# tube-driver_sch-pcb.net
KiCad netlist of a schematic drawn in EAGLE
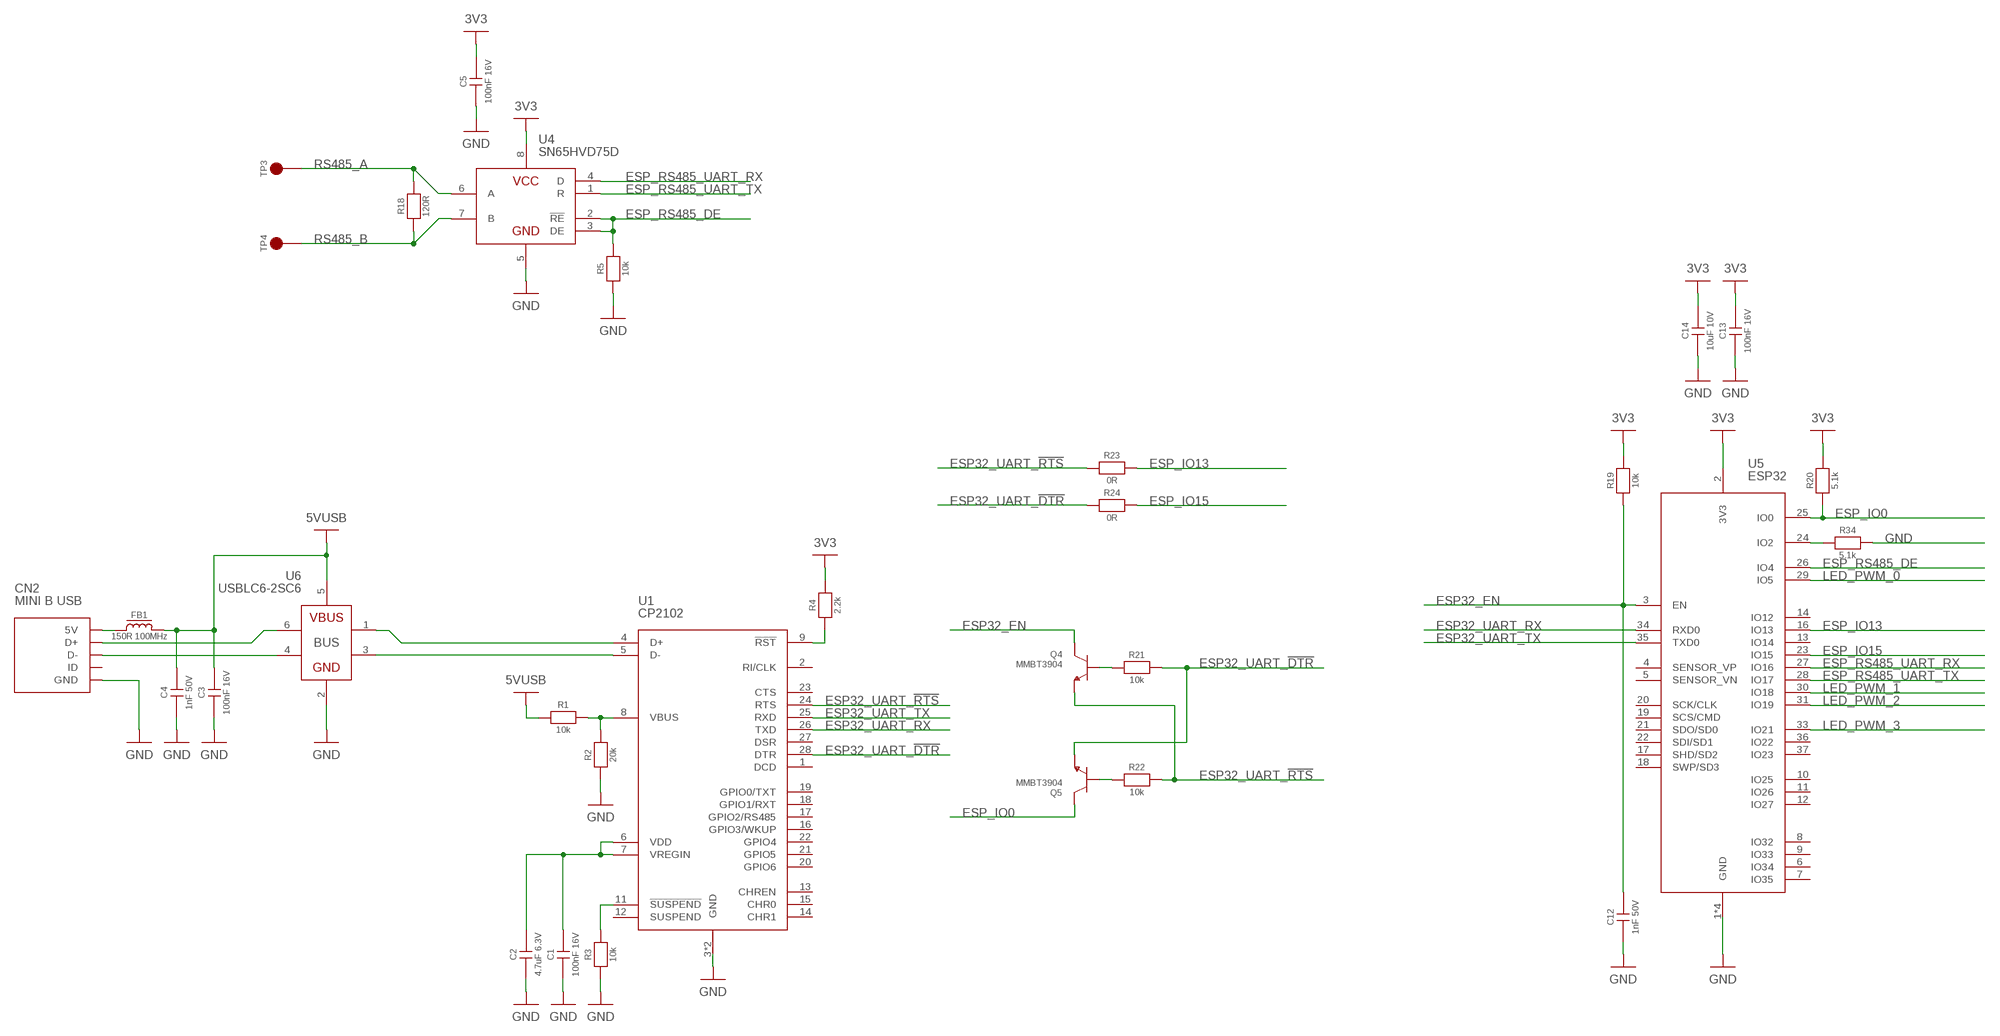
[diagram p0: schematic, sheet 1]
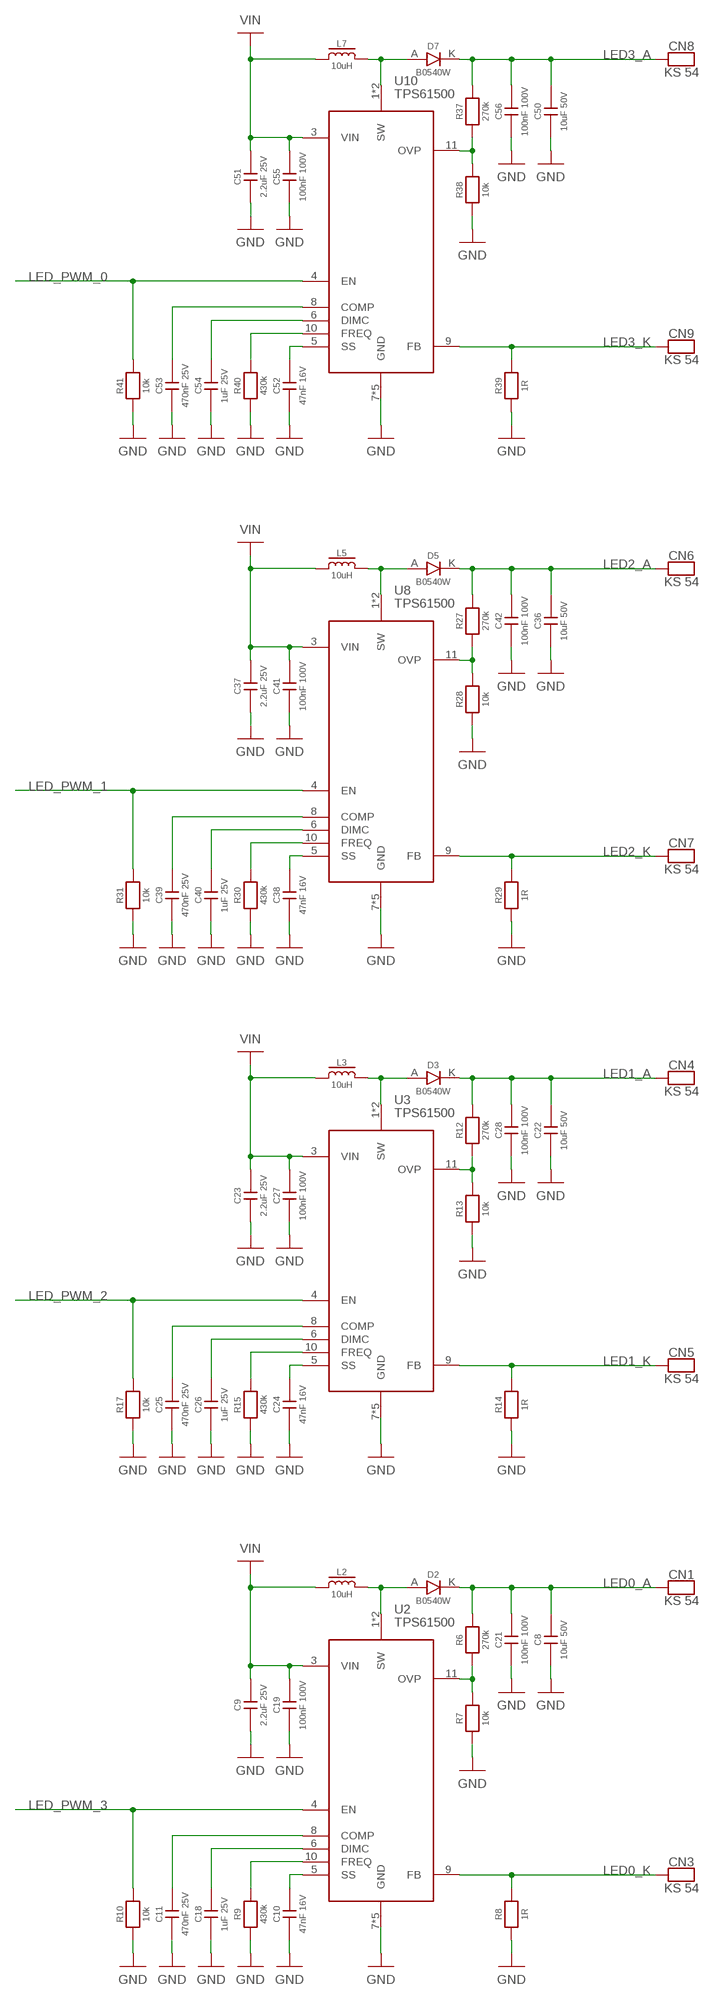
[diagram p1: schematic, sheet 2]
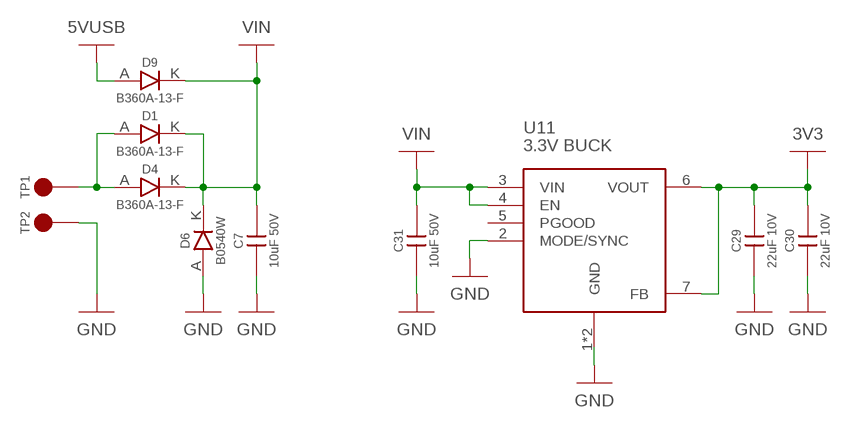
[diagram p2: schematic, sheet 3]
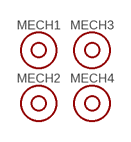
[diagram p3: schematic, sheet 4]

(export (version "E")
  (design (tool "Eeschema 10.0.6"))
  (components
    (comp (ref "C1")
      (value "100nF 16V")
      (footprint "eagle-import:0603")
      (libsource (lib "eagle-import") (part "CL10B104KO8WPNC"))
    )
    (comp (ref "C2")
      (value "4.7uF 6.3V")
      (footprint "eagle-import:0603")
      (libsource (lib "eagle-import") (part "GRM188R60J475ME19D"))
    )
    (comp (ref "C3")
      (value "100nF 16V")
      (footprint "eagle-import:0603")
      (libsource (lib "eagle-import") (part "CL10B104KO8WPNC"))
    )
    (comp (ref "C4")
      (value "1nF 50V")
      (footprint "eagle-import:0603")
      (libsource (lib "eagle-import") (part "CL10B102KB8NNNC"))
    )
    (comp (ref "C5")
      (value "100nF 16V")
      (footprint "eagle-import:0603")
      (libsource (lib "eagle-import") (part "CL10B104KO8WPNC"))
    )
    (comp (ref "C12")
      (value "1nF 50V")
      (footprint "eagle-import:0603")
      (libsource (lib "eagle-import") (part "CL10B102KB8NNNC"))
    )
    (comp (ref "C13")
      (value "100nF 16V")
      (footprint "eagle-import:0603")
      (libsource (lib "eagle-import") (part "CL10B104KO8WPNC"))
    )
    (comp (ref "C14")
      (value "10uF 10V")
      (footprint "eagle-import:0603")
      (libsource (lib "eagle-import") (part "GRM188R61A106KE69D"))
    )
    (comp (ref "CN2")
      (value "MINI B USB")
      (footprint "eagle-import:MUSB-05-S-B-SM-A")
      (libsource (lib "eagle-import") (part "MUSB-05-S-B-SM-A"))
    )
    (comp (ref "FB1")
      (value "150R 100MHz")
      (footprint "eagle-import:1206")
      (libsource (lib "eagle-import") (part "ILB1206ER151V"))
    )
    (comp (ref "Q4")
      (value "MMBT3904")
      (footprint "eagle-import:SOT23-3")
      (libsource (lib "eagle-import") (part "MMBT3904-7-F"))
    )
    (comp (ref "Q5")
      (value "MMBT3904")
      (footprint "eagle-import:SOT23-3")
      (libsource (lib "eagle-import") (part "MMBT3904-7-F"))
    )
    (comp (ref "R1")
      (value "10k")
      (footprint "eagle-import:0603")
      (libsource (lib "eagle-import") (part "ERJ3EKF1002V"))
    )
    (comp (ref "R2")
      (value "20k")
      (footprint "eagle-import:0603")
      (libsource (lib "eagle-import") (part "ERJ3EKF2002V"))
    )
    (comp (ref "R3")
      (value "10k")
      (footprint "eagle-import:0603")
      (libsource (lib "eagle-import") (part "ERJ3EKF1002V"))
    )
    (comp (ref "R4")
      (value "2.2k")
      (footprint "eagle-import:0603")
      (libsource (lib "eagle-import") (part "ERJ3EKF2201V"))
    )
    (comp (ref "R5")
      (value "10k")
      (footprint "eagle-import:0603")
      (libsource (lib "eagle-import") (part "ERJ3EKF1002V"))
    )
    (comp (ref "R18")
      (value "120R")
      (footprint "eagle-import:0603")
      (libsource (lib "eagle-import") (part "ERJ3EKF1200V"))
    )
    (comp (ref "R19")
      (value "10k")
      (footprint "eagle-import:0603")
      (libsource (lib "eagle-import") (part "ERJ3EKF1002V"))
    )
    (comp (ref "R20")
      (value "5.1k")
      (footprint "eagle-import:0603")
      (libsource (lib "eagle-import") (part "ERJ3EKF5101V"))
    )
    (comp (ref "R21")
      (value "10k")
      (footprint "eagle-import:0603")
      (libsource (lib "eagle-import") (part "ERJ3EKF1002V"))
    )
    (comp (ref "R22")
      (value "10k")
      (footprint "eagle-import:0603")
      (libsource (lib "eagle-import") (part "ERJ3EKF1002V"))
    )
    (comp (ref "R23")
      (value "0R")
      (footprint "eagle-import:0603")
      (libsource (lib "eagle-import") (part "CRCW06030000Z0EA"))
    )
    (comp (ref "R24")
      (value "0R")
      (footprint "eagle-import:0603")
      (libsource (lib "eagle-import") (part "CRCW06030000Z0EA"))
    )
    (comp (ref "R34")
      (value "5.1k")
      (footprint "eagle-import:0603")
      (libsource (lib "eagle-import") (part "ERJ3EKF5101V"))
    )
    (comp (ref "TP3")
      (value "2MM_TEST_POINT")
      (footprint "eagle-import:2MM_TEST_PAD")
      (libsource (lib "eagle-import") (part "2MM_TEST_POINT"))
    )
    (comp (ref "TP4")
      (value "2MM_TEST_POINT")
      (footprint "eagle-import:2MM_TEST_PAD")
      (libsource (lib "eagle-import") (part "2MM_TEST_POINT"))
    )
    (comp (ref "U1")
      (value "CP2102")
      (footprint "eagle-import:QFN28")
      (libsource (lib "eagle-import") (part "CP2102N-A01-GQFN28"))
    )
    (comp (ref "U4")
      (value "SN65HVD75D")
      (footprint "eagle-import:SO8")
      (libsource (lib "eagle-import") (part "SN65HVD75D"))
    )
    (comp (ref "U5")
      (value "ESP32")
      (footprint "eagle-import:ESP32-WROOM-32D")
      (libsource (lib "eagle-import") (part "ESP32-WROOM-32D"))
    )
    (comp (ref "U6")
      (value "USBLC6-2SC6")
      (footprint "eagle-import:SOT23-6")
      (libsource (lib "eagle-import") (part "USBLC6-2SC6"))
    )
    (comp (ref "MECH1")
      (value "6mm x 3mm")
      (footprint "eagle-import:MOUNTHOLE_6X3")
      (libsource (lib "eagle-import") (part "MOUNTHOLE"))
    )
    (comp (ref "MECH2")
      (value "6mm x 3mm")
      (footprint "eagle-import:MOUNTHOLE_6X3")
      (libsource (lib "eagle-import") (part "MOUNTHOLE"))
    )
    (comp (ref "MECH3")
      (value "6mm x 3mm")
      (footprint "eagle-import:MOUNTHOLE_6X3")
      (libsource (lib "eagle-import") (part "MOUNTHOLE"))
    )
    (comp (ref "MECH4")
      (value "6mm x 3mm")
      (footprint "eagle-import:MOUNTHOLE_6X3")
      (libsource (lib "eagle-import") (part "MOUNTHOLE"))
    )
    (comp (ref "C7")
      (value "10uF 50V")
      (footprint "eagle-import:1210")
      (libsource (lib "eagle-import") (part "C3225X7S1H106M250AB"))
    )
    (comp (ref "C29")
      (value "22uF 10V")
      (footprint "eagle-import:1206")
      (libsource (lib "eagle-import") (part "CL31B226MPHNNNE"))
    )
    (comp (ref "C30")
      (value "22uF 10V")
      (footprint "eagle-import:1206")
      (libsource (lib "eagle-import") (part "CL31B226MPHNNNE"))
    )
    (comp (ref "C31")
      (value "10uF 50V")
      (footprint "eagle-import:1210")
      (libsource (lib "eagle-import") (part "C3225X7S1H106M250AB"))
    )
    (comp (ref "D1")
      (value "B360A-13-F")
      (footprint "eagle-import:DO214AC")
      (libsource (lib "eagle-import") (part "B360A-13-F"))
    )
    (comp (ref "D4")
      (value "B360A-13-F")
      (footprint "eagle-import:DO214AC")
      (libsource (lib "eagle-import") (part "B360A-13-F"))
    )
    (comp (ref "D6")
      (value "B0540W")
      (footprint "eagle-import:SOD-123")
      (libsource (lib "eagle-import") (part "B0540W"))
    )
    (comp (ref "D9")
      (value "B360A-13-F")
      (footprint "eagle-import:DO214AC")
      (libsource (lib "eagle-import") (part "B360A-13-F"))
    )
    (comp (ref "TP1")
      (value "2MM_TEST_POINT")
      (footprint "eagle-import:2MM_TEST_PAD")
      (libsource (lib "eagle-import") (part "2MM_TEST_POINT"))
    )
    (comp (ref "TP2")
      (value "2MM_TEST_POINT")
      (footprint "eagle-import:2MM_TEST_PAD")
      (libsource (lib "eagle-import") (part "2MM_TEST_POINT"))
    )
    (comp (ref "U11")
      (value "3.3V BUCK")
      (footprint "eagle-import:TI_MICROSIP_10")
      (libsource (lib "eagle-import") (part "LMZM23600V3SILT"))
    )
    (comp (ref "C8")
      (value "10uF 50V")
      (footprint "eagle-import:1210")
      (libsource (lib "eagle-import") (part "C3225X7S1H106M250AB"))
    )
    (comp (ref "C9")
      (value "2.2uF 25V")
      (footprint "eagle-import:0603")
      (libsource (lib "eagle-import") (part "GRM188R61E225KA12D"))
    )
    (comp (ref "C10")
      (value "47nF 16V")
      (footprint "eagle-import:0603")
      (libsource (lib "eagle-import") (part "CL10B473KO8NNNC"))
    )
    (comp (ref "C11")
      (value "470nF 25V")
      (footprint "eagle-import:0603")
      (libsource (lib "eagle-import") (part "GRM188R71E474KA12D"))
    )
    (comp (ref "C18")
      (value "1uF 25V")
      (footprint "eagle-import:0603")
      (libsource (lib "eagle-import") (part "CL10A105KA8NNNC"))
    )
    (comp (ref "C19")
      (value "100nF 100V")
      (footprint "eagle-import:0603")
      (libsource (lib "eagle-import") (part "06031C104KAT2A"))
    )
    (comp (ref "C21")
      (value "100nF 100V")
      (footprint "eagle-import:0603")
      (libsource (lib "eagle-import") (part "06031C104KAT2A"))
    )
    (comp (ref "C22")
      (value "10uF 50V")
      (footprint "eagle-import:1210")
      (libsource (lib "eagle-import") (part "C3225X7S1H106M250AB"))
    )
    (comp (ref "C23")
      (value "2.2uF 25V")
      (footprint "eagle-import:0603")
      (libsource (lib "eagle-import") (part "GRM188R61E225KA12D"))
    )
    (comp (ref "C24")
      (value "47nF 16V")
      (footprint "eagle-import:0603")
      (libsource (lib "eagle-import") (part "CL10B473KO8NNNC"))
    )
    (comp (ref "C25")
      (value "470nF 25V")
      (footprint "eagle-import:0603")
      (libsource (lib "eagle-import") (part "GRM188R71E474KA12D"))
    )
    (comp (ref "C26")
      (value "1uF 25V")
      (footprint "eagle-import:0603")
      (libsource (lib "eagle-import") (part "CL10A105KA8NNNC"))
    )
    (comp (ref "C27")
      (value "100nF 100V")
      (footprint "eagle-import:0603")
      (libsource (lib "eagle-import") (part "06031C104KAT2A"))
    )
    (comp (ref "C28")
      (value "100nF 100V")
      (footprint "eagle-import:0603")
      (libsource (lib "eagle-import") (part "06031C104KAT2A"))
    )
    (comp (ref "C36")
      (value "10uF 50V")
      (footprint "eagle-import:1210")
      (libsource (lib "eagle-import") (part "C3225X7S1H106M250AB"))
    )
    (comp (ref "C37")
      (value "2.2uF 25V")
      (footprint "eagle-import:0603")
      (libsource (lib "eagle-import") (part "GRM188R61E225KA12D"))
    )
    (comp (ref "C38")
      (value "47nF 16V")
      (footprint "eagle-import:0603")
      (libsource (lib "eagle-import") (part "CL10B473KO8NNNC"))
    )
    (comp (ref "C39")
      (value "470nF 25V")
      (footprint "eagle-import:0603")
      (libsource (lib "eagle-import") (part "GRM188R71E474KA12D"))
    )
    (comp (ref "C40")
      (value "1uF 25V")
      (footprint "eagle-import:0603")
      (libsource (lib "eagle-import") (part "CL10A105KA8NNNC"))
    )
    (comp (ref "C41")
      (value "100nF 100V")
      (footprint "eagle-import:0603")
      (libsource (lib "eagle-import") (part "06031C104KAT2A"))
    )
    (comp (ref "C42")
      (value "100nF 100V")
      (footprint "eagle-import:0603")
      (libsource (lib "eagle-import") (part "06031C104KAT2A"))
    )
    (comp (ref "C50")
      (value "10uF 50V")
      (footprint "eagle-import:1210")
      (libsource (lib "eagle-import") (part "C3225X7S1H106M250AB"))
    )
    (comp (ref "C51")
      (value "2.2uF 25V")
      (footprint "eagle-import:0603")
      (libsource (lib "eagle-import") (part "GRM188R61E225KA12D"))
    )
    (comp (ref "C52")
      (value "47nF 16V")
      (footprint "eagle-import:0603")
      (libsource (lib "eagle-import") (part "CL10B473KO8NNNC"))
    )
    (comp (ref "C53")
      (value "470nF 25V")
      (footprint "eagle-import:0603")
      (libsource (lib "eagle-import") (part "GRM188R71E474KA12D"))
    )
    (comp (ref "C54")
      (value "1uF 25V")
      (footprint "eagle-import:0603")
      (libsource (lib "eagle-import") (part "CL10A105KA8NNNC"))
    )
    (comp (ref "C55")
      (value "100nF 100V")
      (footprint "eagle-import:0603")
      (libsource (lib "eagle-import") (part "06031C104KAT2A"))
    )
    (comp (ref "C56")
      (value "100nF 100V")
      (footprint "eagle-import:0603")
      (libsource (lib "eagle-import") (part "06031C104KAT2A"))
    )
    (comp (ref "CN1")
      (value "KS 54")
      (footprint "eagle-import:KEYSTONE_54")
      (libsource (lib "eagle-import") (part "KEYSTONE_54"))
    )
    (comp (ref "CN3")
      (value "KS 54")
      (footprint "eagle-import:KEYSTONE_54")
      (libsource (lib "eagle-import") (part "KEYSTONE_54"))
    )
    (comp (ref "CN4")
      (value "KS 54")
      (footprint "eagle-import:KEYSTONE_54")
      (libsource (lib "eagle-import") (part "KEYSTONE_54"))
    )
    (comp (ref "CN5")
      (value "KS 54")
      (footprint "eagle-import:KEYSTONE_54")
      (libsource (lib "eagle-import") (part "KEYSTONE_54"))
    )
    (comp (ref "CN6")
      (value "KS 54")
      (footprint "eagle-import:KEYSTONE_54")
      (libsource (lib "eagle-import") (part "KEYSTONE_54"))
    )
    (comp (ref "CN7")
      (value "KS 54")
      (footprint "eagle-import:KEYSTONE_54")
      (libsource (lib "eagle-import") (part "KEYSTONE_54"))
    )
    (comp (ref "CN8")
      (value "KS 54")
      (footprint "eagle-import:KEYSTONE_54")
      (libsource (lib "eagle-import") (part "KEYSTONE_54"))
    )
    (comp (ref "CN9")
      (value "KS 54")
      (footprint "eagle-import:KEYSTONE_54")
      (libsource (lib "eagle-import") (part "KEYSTONE_54"))
    )
    (comp (ref "D2")
      (value "B0540W")
      (footprint "eagle-import:SOD-123")
      (libsource (lib "eagle-import") (part "B0540W"))
    )
    (comp (ref "D3")
      (value "B0540W")
      (footprint "eagle-import:SOD-123")
      (libsource (lib "eagle-import") (part "B0540W"))
    )
    (comp (ref "D5")
      (value "B0540W")
      (footprint "eagle-import:SOD-123")
      (libsource (lib "eagle-import") (part "B0540W"))
    )
    (comp (ref "D7")
      (value "B0540W")
      (footprint "eagle-import:SOD-123")
      (libsource (lib "eagle-import") (part "B0540W"))
    )
    (comp (ref "L2")
      (value "10uH")
      (footprint "eagle-import:SRN6045")
      (libsource (lib "eagle-import") (part "SRN6045-100M"))
    )
    (comp (ref "L3")
      (value "10uH")
      (footprint "eagle-import:SRN6045")
      (libsource (lib "eagle-import") (part "SRN6045-100M"))
    )
    (comp (ref "L5")
      (value "10uH")
      (footprint "eagle-import:SRN6045")
      (libsource (lib "eagle-import") (part "SRN6045-100M"))
    )
    (comp (ref "L7")
      (value "10uH")
      (footprint "eagle-import:SRN6045")
      (libsource (lib "eagle-import") (part "SRN6045-100M"))
    )
    (comp (ref "R6")
      (value "270k")
      (footprint "eagle-import:0603")
      (libsource (lib "eagle-import") (part "ERJ3EKF2703V"))
    )
    (comp (ref "R7")
      (value "10k")
      (footprint "eagle-import:0603")
      (libsource (lib "eagle-import") (part "ERJ3EKF1002V"))
    )
    (comp (ref "R8")
      (value "1R")
      (footprint "eagle-import:1206")
      (libsource (lib "eagle-import") (part "CRCW12061R00FKEA"))
    )
    (comp (ref "R9")
      (value "430k")
      (footprint "eagle-import:0603")
      (libsource (lib "eagle-import") (part "ERJ3EKF4303V"))
    )
    (comp (ref "R10")
      (value "10k")
      (footprint "eagle-import:0603")
      (libsource (lib "eagle-import") (part "ERJ3EKF1002V"))
    )
    (comp (ref "R12")
      (value "270k")
      (footprint "eagle-import:0603")
      (libsource (lib "eagle-import") (part "ERJ3EKF2703V"))
    )
    (comp (ref "R13")
      (value "10k")
      (footprint "eagle-import:0603")
      (libsource (lib "eagle-import") (part "ERJ3EKF1002V"))
    )
    (comp (ref "R14")
      (value "1R")
      (footprint "eagle-import:1206")
      (libsource (lib "eagle-import") (part "CRCW12061R00FKEA"))
    )
    (comp (ref "R15")
      (value "430k")
      (footprint "eagle-import:0603")
      (libsource (lib "eagle-import") (part "ERJ3EKF4303V"))
    )
    (comp (ref "R17")
      (value "10k")
      (footprint "eagle-import:0603")
      (libsource (lib "eagle-import") (part "ERJ3EKF1002V"))
    )
    (comp (ref "R27")
      (value "270k")
      (footprint "eagle-import:0603")
      (libsource (lib "eagle-import") (part "ERJ3EKF2703V"))
    )
    (comp (ref "R28")
      (value "10k")
      (footprint "eagle-import:0603")
      (libsource (lib "eagle-import") (part "ERJ3EKF1002V"))
    )
    (comp (ref "R29")
      (value "1R")
      (footprint "eagle-import:1206")
      (libsource (lib "eagle-import") (part "CRCW12061R00FKEA"))
    )
    (comp (ref "R30")
      (value "430k")
      (footprint "eagle-import:0603")
      (libsource (lib "eagle-import") (part "ERJ3EKF4303V"))
    )
    (comp (ref "R31")
      (value "10k")
      (footprint "eagle-import:0603")
      (libsource (lib "eagle-import") (part "ERJ3EKF1002V"))
    )
    (comp (ref "R37")
      (value "270k")
      (footprint "eagle-import:0603")
      (libsource (lib "eagle-import") (part "ERJ3EKF2703V"))
    )
    (comp (ref "R38")
      (value "10k")
      (footprint "eagle-import:0603")
      (libsource (lib "eagle-import") (part "ERJ3EKF1002V"))
    )
    (comp (ref "R39")
      (value "1R")
      (footprint "eagle-import:1206")
      (libsource (lib "eagle-import") (part "CRCW12061R00FKEA"))
    )
    (comp (ref "R40")
      (value "430k")
      (footprint "eagle-import:0603")
      (libsource (lib "eagle-import") (part "ERJ3EKF4303V"))
    )
    (comp (ref "R41")
      (value "10k")
      (footprint "eagle-import:0603")
      (libsource (lib "eagle-import") (part "ERJ3EKF1002V"))
    )
    (comp (ref "U2")
      (value "TPS61500")
      (footprint "eagle-import:HTSSOP14-4.5")
      (libsource (lib "eagle-import") (part "TPS61500"))
    )
    (comp (ref "U3")
      (value "TPS61500")
      (footprint "eagle-import:HTSSOP14-4.5")
      (libsource (lib "eagle-import") (part "TPS61500"))
    )
    (comp (ref "U8")
      (value "TPS61500")
      (footprint "eagle-import:HTSSOP14-4.5")
      (libsource (lib "eagle-import") (part "TPS61500"))
    )
    (comp (ref "U10")
      (value "TPS61500")
      (footprint "eagle-import:HTSSOP14-4.5")
      (libsource (lib "eagle-import") (part "TPS61500"))
    )
  )
  (nets
    (net (code "1") (name "3V3") (class "Default")
      (node (ref "C13") (pin "2") (pinfunction "2_2") (pintype "bidirectional"))
      (node (ref "C14") (pin "2") (pinfunction "2_2") (pintype "bidirectional"))
      (node (ref "C29") (pin "2") (pinfunction "2_2") (pintype "bidirectional"))
      (node (ref "C30") (pin "2") (pinfunction "2_2") (pintype "bidirectional"))
      (node (ref "C5") (pin "2") (pinfunction "2_2") (pintype "bidirectional"))
      (node (ref "R19") (pin "2") (pinfunction "2_2") (pintype "bidirectional"))
      (node (ref "R20") (pin "2") (pinfunction "2_2") (pintype "bidirectional"))
      (node (ref "R4") (pin "2") (pinfunction "2_2") (pintype "bidirectional"))
      (node (ref "U11") (pin "6") (pinfunction "VOUT_6") (pintype "bidirectional"))
      (node (ref "U11") (pin "7") (pinfunction "FB_7") (pintype "bidirectional"))
      (node (ref "U4") (pin "8") (pinfunction "VCC_8") (pintype "bidirectional"))
      (node (ref "U5") (pin "2") (pinfunction "3V3_2") (pintype "bidirectional"))
    )
    (net (code "2") (name "5VUSB") (class "Default")
      (node (ref "C3") (pin "2") (pinfunction "2_2") (pintype "bidirectional"))
      (node (ref "C4") (pin "2") (pinfunction "2_2") (pintype "bidirectional"))
      (node (ref "D9") (pin "A") (pinfunction "A_A") (pintype "bidirectional"))
      (node (ref "FB1") (pin "2") (pinfunction "2_2") (pintype "bidirectional"))
      (node (ref "R1") (pin "1") (pinfunction "1_1") (pintype "bidirectional"))
      (node (ref "U6") (pin "5") (pinfunction "VBUS_5") (pintype "bidirectional"))
    )
    (net (code "3") (name "ESP32_EN") (class "Default")
      (node (ref "C12") (pin "2") (pinfunction "2_2") (pintype "bidirectional"))
      (node (ref "Q4") (pin "2") (pinfunction "C_2") (pintype "bidirectional"))
      (node (ref "R19") (pin "1") (pinfunction "1_1") (pintype "bidirectional"))
      (node (ref "U5") (pin "3") (pinfunction "EN_3") (pintype "bidirectional"))
    )
    (net (code "4") (name "ESP32_UART_RX") (class "Default")
      (node (ref "U1") (pin "26") (pinfunction "TXD_26") (pintype "bidirectional"))
      (node (ref "U5") (pin "34") (pinfunction "RXD0_34") (pintype "bidirectional"))
    )
    (net (code "5") (name "ESP32_UART_TX") (class "Default")
      (node (ref "U1") (pin "25") (pinfunction "RXD_25") (pintype "bidirectional"))
      (node (ref "U5") (pin "35") (pinfunction "TXD0_35") (pintype "bidirectional"))
    )
    (net (code "6") (name "ESP32_UART_~{DTR}") (class "Default")
      (node (ref "Q5") (pin "3") (pinfunction "E_3") (pintype "bidirectional"))
      (node (ref "R21") (pin "2") (pinfunction "2_2") (pintype "bidirectional"))
      (node (ref "R24") (pin "1") (pinfunction "1_1") (pintype "bidirectional"))
      (node (ref "U1") (pin "28") (pinfunction "DTR_28") (pintype "bidirectional"))
    )
    (net (code "7") (name "ESP32_UART_~{RTS}") (class "Default")
      (node (ref "Q4") (pin "3") (pinfunction "E_3") (pintype "bidirectional"))
      (node (ref "R22") (pin "2") (pinfunction "2_2") (pintype "bidirectional"))
      (node (ref "R23") (pin "1") (pinfunction "1_1") (pintype "bidirectional"))
      (node (ref "U1") (pin "24") (pinfunction "RTS_24") (pintype "bidirectional"))
    )
    (net (code "8") (name "ESP_IO0") (class "Default")
      (node (ref "Q5") (pin "2") (pinfunction "C_2") (pintype "bidirectional"))
      (node (ref "R20") (pin "1") (pinfunction "1_1") (pintype "bidirectional"))
      (node (ref "U5") (pin "25") (pinfunction "IO0_25") (pintype "bidirectional"))
    )
    (net (code "9") (name "ESP_IO13") (class "Default")
      (node (ref "R23") (pin "2") (pinfunction "2_2") (pintype "bidirectional"))
      (node (ref "U5") (pin "16") (pinfunction "IO13_16") (pintype "bidirectional"))
    )
    (net (code "10") (name "ESP_IO15") (class "Default")
      (node (ref "R24") (pin "2") (pinfunction "2_2") (pintype "bidirectional"))
      (node (ref "U5") (pin "23") (pinfunction "IO15_23") (pintype "bidirectional"))
    )
    (net (code "11") (name "ESP_RS485_DE") (class "Default")
      (node (ref "R5") (pin "2") (pinfunction "2_2") (pintype "bidirectional"))
      (node (ref "U4") (pin "2") (pinfunction "~{RE}_2") (pintype "bidirectional"))
      (node (ref "U4") (pin "3") (pinfunction "DE_3") (pintype "bidirectional"))
      (node (ref "U5") (pin "26") (pinfunction "IO4_26") (pintype "bidirectional"))
    )
    (net (code "12") (name "ESP_RS485_UART_RX") (class "Default")
      (node (ref "U4") (pin "4") (pinfunction "D_4") (pintype "bidirectional"))
      (node (ref "U5") (pin "27") (pinfunction "IO16_27") (pintype "bidirectional"))
    )
    (net (code "13") (name "ESP_RS485_UART_TX") (class "Default")
      (node (ref "U4") (pin "1") (pinfunction "R_1") (pintype "bidirectional"))
      (node (ref "U5") (pin "28") (pinfunction "IO17_28") (pintype "bidirectional"))
    )
    (net (code "14") (name "GND") (class "Default")
      (node (ref "C1") (pin "1") (pinfunction "1_1") (pintype "bidirectional"))
      (node (ref "C10") (pin "1") (pinfunction "1_1") (pintype "bidirectional"))
      (node (ref "C11") (pin "1") (pinfunction "1_1") (pintype "bidirectional"))
      (node (ref "C12") (pin "1") (pinfunction "1_1") (pintype "bidirectional"))
      (node (ref "C13") (pin "1") (pinfunction "1_1") (pintype "bidirectional"))
      (node (ref "C14") (pin "1") (pinfunction "1_1") (pintype "bidirectional"))
      (node (ref "C18") (pin "1") (pinfunction "1_1") (pintype "bidirectional"))
      (node (ref "C19") (pin "1") (pinfunction "1_1") (pintype "bidirectional"))
      (node (ref "C2") (pin "1") (pinfunction "1_1") (pintype "bidirectional"))
      (node (ref "C21") (pin "1") (pinfunction "1_1") (pintype "bidirectional"))
      (node (ref "C22") (pin "1") (pinfunction "1_1") (pintype "bidirectional"))
      (node (ref "C23") (pin "1") (pinfunction "1_1") (pintype "bidirectional"))
      (node (ref "C24") (pin "1") (pinfunction "1_1") (pintype "bidirectional"))
      (node (ref "C25") (pin "1") (pinfunction "1_1") (pintype "bidirectional"))
      (node (ref "C26") (pin "1") (pinfunction "1_1") (pintype "bidirectional"))
      (node (ref "C27") (pin "1") (pinfunction "1_1") (pintype "bidirectional"))
      (node (ref "C28") (pin "1") (pinfunction "1_1") (pintype "bidirectional"))
      (node (ref "C29") (pin "1") (pinfunction "1_1") (pintype "bidirectional"))
      (node (ref "C3") (pin "1") (pinfunction "1_1") (pintype "bidirectional"))
      (node (ref "C30") (pin "1") (pinfunction "1_1") (pintype "bidirectional"))
      (node (ref "C31") (pin "1") (pinfunction "1_1") (pintype "bidirectional"))
      (node (ref "C36") (pin "1") (pinfunction "1_1") (pintype "bidirectional"))
      (node (ref "C37") (pin "1") (pinfunction "1_1") (pintype "bidirectional"))
      (node (ref "C38") (pin "1") (pinfunction "1_1") (pintype "bidirectional"))
      (node (ref "C39") (pin "1") (pinfunction "1_1") (pintype "bidirectional"))
      (node (ref "C4") (pin "1") (pinfunction "1_1") (pintype "bidirectional"))
      (node (ref "C40") (pin "1") (pinfunction "1_1") (pintype "bidirectional"))
      (node (ref "C41") (pin "1") (pinfunction "1_1") (pintype "bidirectional"))
      (node (ref "C42") (pin "1") (pinfunction "1_1") (pintype "bidirectional"))
      (node (ref "C5") (pin "1") (pinfunction "1_1") (pintype "bidirectional"))
      (node (ref "C50") (pin "1") (pinfunction "1_1") (pintype "bidirectional"))
      (node (ref "C51") (pin "1") (pinfunction "1_1") (pintype "bidirectional"))
      (node (ref "C52") (pin "1") (pinfunction "1_1") (pintype "bidirectional"))
      (node (ref "C53") (pin "1") (pinfunction "1_1") (pintype "bidirectional"))
      (node (ref "C54") (pin "1") (pinfunction "1_1") (pintype "bidirectional"))
      (node (ref "C55") (pin "1") (pinfunction "1_1") (pintype "bidirectional"))
      (node (ref "C56") (pin "1") (pinfunction "1_1") (pintype "bidirectional"))
      (node (ref "C7") (pin "1") (pinfunction "1_1") (pintype "bidirectional"))
      (node (ref "C8") (pin "1") (pinfunction "1_1") (pintype "bidirectional"))
      (node (ref "C9") (pin "1") (pinfunction "1_1") (pintype "bidirectional"))
      (node (ref "CN2") (pin "GND") (pinfunction "GND_GND") (pintype "bidirectional"))
      (node (ref "CN2") (pin "SHIELD1") (pinfunction "GND_SHIELD1") (pintype "bidirectional"))
      (node (ref "CN2") (pin "SHIELD2") (pinfunction "GND_SHIELD2") (pintype "bidirectional"))
      (node (ref "CN2") (pin "SHIELD3") (pinfunction "GND_SHIELD3") (pintype "bidirectional"))
      (node (ref "CN2") (pin "SHIELD4") (pinfunction "GND_SHIELD4") (pintype "bidirectional"))
      (node (ref "D6") (pin "A") (pinfunction "A_A") (pintype "bidirectional"))
      (node (ref "R10") (pin "1") (pinfunction "1_1") (pintype "bidirectional"))
      (node (ref "R13") (pin "1") (pinfunction "1_1") (pintype "bidirectional"))
      (node (ref "R14") (pin "1") (pinfunction "1_1") (pintype "bidirectional"))
      (node (ref "R15") (pin "1") (pinfunction "1_1") (pintype "bidirectional"))
      (node (ref "R17") (pin "1") (pinfunction "1_1") (pintype "bidirectional"))
      (node (ref "R2") (pin "1") (pinfunction "1_1") (pintype "bidirectional"))
      (node (ref "R28") (pin "1") (pinfunction "1_1") (pintype "bidirectional"))
      (node (ref "R29") (pin "1") (pinfunction "1_1") (pintype "bidirectional"))
      (node (ref "R3") (pin "1") (pinfunction "1_1") (pintype "bidirectional"))
      (node (ref "R30") (pin "1") (pinfunction "1_1") (pintype "bidirectional"))
      (node (ref "R31") (pin "1") (pinfunction "1_1") (pintype "bidirectional"))
      (node (ref "R34") (pin "2") (pinfunction "2_2") (pintype "bidirectional"))
      (node (ref "R38") (pin "1") (pinfunction "1_1") (pintype "bidirectional"))
      (node (ref "R39") (pin "1") (pinfunction "1_1") (pintype "bidirectional"))
      (node (ref "R40") (pin "1") (pinfunction "1_1") (pintype "bidirectional"))
      (node (ref "R41") (pin "1") (pinfunction "1_1") (pintype "bidirectional"))
      (node (ref "R5") (pin "1") (pinfunction "1_1") (pintype "bidirectional"))
      (node (ref "R7") (pin "1") (pinfunction "1_1") (pintype "bidirectional"))
      (node (ref "R8") (pin "1") (pinfunction "1_1") (pintype "bidirectional"))
      (node (ref "R9") (pin "1") (pinfunction "1_1") (pintype "bidirectional"))
      (node (ref "TP2") (pin "1") (pinfunction "P$1_1") (pintype "bidirectional"))
      (node (ref "U1") (pin "29") (pinfunction "GND_29") (pintype "bidirectional"))
      (node (ref "U1") (pin "3") (pinfunction "GND_3") (pintype "bidirectional"))
      (node (ref "U10") (pin "12") (pinfunction "GND_12") (pintype "bidirectional"))
      (node (ref "U10") (pin "13") (pinfunction "GND_13") (pintype "bidirectional"))
      (node (ref "U10") (pin "14") (pinfunction "GND_14") (pintype "bidirectional"))
      (node (ref "U10") (pin "7") (pinfunction "GND_7") (pintype "bidirectional"))
      (node (ref "U10") (pin "PAD") (pinfunction "GND_PAD") (pintype "bidirectional"))
      (node (ref "U11") (pin "1") (pinfunction "GND_1") (pintype "bidirectional"))
      (node (ref "U11") (pin "2") (pinfunction "MODE/SYNC_2") (pintype "bidirectional"))
      (node (ref "U11") (pin "PAD") (pinfunction "GND_PAD") (pintype "bidirectional"))
      (node (ref "U2") (pin "12") (pinfunction "GND_12") (pintype "bidirectional"))
      (node (ref "U2") (pin "13") (pinfunction "GND_13") (pintype "bidirectional"))
      (node (ref "U2") (pin "14") (pinfunction "GND_14") (pintype "bidirectional"))
      (node (ref "U2") (pin "7") (pinfunction "GND_7") (pintype "bidirectional"))
      (node (ref "U2") (pin "PAD") (pinfunction "GND_PAD") (pintype "bidirectional"))
      (node (ref "U3") (pin "12") (pinfunction "GND_12") (pintype "bidirectional"))
      (node (ref "U3") (pin "13") (pinfunction "GND_13") (pintype "bidirectional"))
      (node (ref "U3") (pin "14") (pinfunction "GND_14") (pintype "bidirectional"))
      (node (ref "U3") (pin "7") (pinfunction "GND_7") (pintype "bidirectional"))
      (node (ref "U3") (pin "PAD") (pinfunction "GND_PAD") (pintype "bidirectional"))
      (node (ref "U4") (pin "5") (pinfunction "GND_5") (pintype "bidirectional"))
      (node (ref "U5") (pin "1") (pinfunction "GND_1") (pintype "bidirectional"))
      (node (ref "U5") (pin "15") (pinfunction "GND_15") (pintype "bidirectional"))
      (node (ref "U5") (pin "38") (pinfunction "GND_38") (pintype "bidirectional"))
      (node (ref "U5") (pin "39") (pinfunction "GND_39") (pintype "bidirectional"))
      (node (ref "U6") (pin "2") (pinfunction "GND_2") (pintype "bidirectional"))
      (node (ref "U8") (pin "12") (pinfunction "GND_12") (pintype "bidirectional"))
      (node (ref "U8") (pin "13") (pinfunction "GND_13") (pintype "bidirectional"))
      (node (ref "U8") (pin "14") (pinfunction "GND_14") (pintype "bidirectional"))
      (node (ref "U8") (pin "7") (pinfunction "GND_7") (pintype "bidirectional"))
      (node (ref "U8") (pin "PAD") (pinfunction "GND_PAD") (pintype "bidirectional"))
    )
    (net (code "15") (name "LED0_A") (class "Default")
      (node (ref "C21") (pin "2") (pinfunction "2_2") (pintype "bidirectional"))
      (node (ref "C8") (pin "2") (pinfunction "2_2") (pintype "bidirectional"))
      (node (ref "CN1") (pin "P$1") (pinfunction "P$1_P$1") (pintype "bidirectional"))
      (node (ref "CN1") (pin "P$2") (pinfunction "P$1_P$2") (pintype "bidirectional"))
      (node (ref "CN1") (pin "P$3") (pinfunction "P$1_P$3") (pintype "bidirectional"))
      (node (ref "D2") (pin "K") (pinfunction "K_K") (pintype "bidirectional"))
      (node (ref "R6") (pin "2") (pinfunction "2_2") (pintype "bidirectional"))
    )
    (net (code "16") (name "LED0_K") (class "Default")
      (node (ref "CN3") (pin "P$1") (pinfunction "P$1_P$1") (pintype "bidirectional"))
      (node (ref "CN3") (pin "P$2") (pinfunction "P$1_P$2") (pintype "bidirectional"))
      (node (ref "CN3") (pin "P$3") (pinfunction "P$1_P$3") (pintype "bidirectional"))
      (node (ref "R8") (pin "2") (pinfunction "2_2") (pintype "bidirectional"))
      (node (ref "U2") (pin "9") (pinfunction "FB_9") (pintype "bidirectional"))
    )
    (net (code "17") (name "LED1_A") (class "Default")
      (node (ref "C22") (pin "2") (pinfunction "2_2") (pintype "bidirectional"))
      (node (ref "C28") (pin "2") (pinfunction "2_2") (pintype "bidirectional"))
      (node (ref "CN4") (pin "P$1") (pinfunction "P$1_P$1") (pintype "bidirectional"))
      (node (ref "CN4") (pin "P$2") (pinfunction "P$1_P$2") (pintype "bidirectional"))
      (node (ref "CN4") (pin "P$3") (pinfunction "P$1_P$3") (pintype "bidirectional"))
      (node (ref "D3") (pin "K") (pinfunction "K_K") (pintype "bidirectional"))
      (node (ref "R12") (pin "2") (pinfunction "2_2") (pintype "bidirectional"))
    )
    (net (code "18") (name "LED1_K") (class "Default")
      (node (ref "CN5") (pin "P$1") (pinfunction "P$1_P$1") (pintype "bidirectional"))
      (node (ref "CN5") (pin "P$2") (pinfunction "P$1_P$2") (pintype "bidirectional"))
      (node (ref "CN5") (pin "P$3") (pinfunction "P$1_P$3") (pintype "bidirectional"))
      (node (ref "R14") (pin "2") (pinfunction "2_2") (pintype "bidirectional"))
      (node (ref "U3") (pin "9") (pinfunction "FB_9") (pintype "bidirectional"))
    )
    (net (code "19") (name "LED2_A") (class "Default")
      (node (ref "C36") (pin "2") (pinfunction "2_2") (pintype "bidirectional"))
      (node (ref "C42") (pin "2") (pinfunction "2_2") (pintype "bidirectional"))
      (node (ref "CN6") (pin "P$1") (pinfunction "P$1_P$1") (pintype "bidirectional"))
      (node (ref "CN6") (pin "P$2") (pinfunction "P$1_P$2") (pintype "bidirectional"))
      (node (ref "CN6") (pin "P$3") (pinfunction "P$1_P$3") (pintype "bidirectional"))
      (node (ref "D5") (pin "K") (pinfunction "K_K") (pintype "bidirectional"))
      (node (ref "R27") (pin "2") (pinfunction "2_2") (pintype "bidirectional"))
    )
    (net (code "20") (name "LED2_K") (class "Default")
      (node (ref "CN7") (pin "P$1") (pinfunction "P$1_P$1") (pintype "bidirectional"))
      (node (ref "CN7") (pin "P$2") (pinfunction "P$1_P$2") (pintype "bidirectional"))
      (node (ref "CN7") (pin "P$3") (pinfunction "P$1_P$3") (pintype "bidirectional"))
      (node (ref "R29") (pin "2") (pinfunction "2_2") (pintype "bidirectional"))
      (node (ref "U8") (pin "9") (pinfunction "FB_9") (pintype "bidirectional"))
    )
    (net (code "21") (name "LED3_A") (class "Default")
      (node (ref "C50") (pin "2") (pinfunction "2_2") (pintype "bidirectional"))
      (node (ref "C56") (pin "2") (pinfunction "2_2") (pintype "bidirectional"))
      (node (ref "CN8") (pin "P$1") (pinfunction "P$1_P$1") (pintype "bidirectional"))
      (node (ref "CN8") (pin "P$2") (pinfunction "P$1_P$2") (pintype "bidirectional"))
      (node (ref "CN8") (pin "P$3") (pinfunction "P$1_P$3") (pintype "bidirectional"))
      (node (ref "D7") (pin "K") (pinfunction "K_K") (pintype "bidirectional"))
      (node (ref "R37") (pin "2") (pinfunction "2_2") (pintype "bidirectional"))
    )
    (net (code "22") (name "LED3_K") (class "Default")
      (node (ref "CN9") (pin "P$1") (pinfunction "P$1_P$1") (pintype "bidirectional"))
      (node (ref "CN9") (pin "P$2") (pinfunction "P$1_P$2") (pintype "bidirectional"))
      (node (ref "CN9") (pin "P$3") (pinfunction "P$1_P$3") (pintype "bidirectional"))
      (node (ref "R39") (pin "2") (pinfunction "2_2") (pintype "bidirectional"))
      (node (ref "U10") (pin "9") (pinfunction "FB_9") (pintype "bidirectional"))
    )
    (net (code "23") (name "LED_PWM_0") (class "Default")
      (node (ref "R41") (pin "2") (pinfunction "2_2") (pintype "bidirectional"))
      (node (ref "U10") (pin "4") (pinfunction "EN_4") (pintype "bidirectional"))
      (node (ref "U5") (pin "29") (pinfunction "IO5_29") (pintype "bidirectional"))
    )
    (net (code "24") (name "LED_PWM_1") (class "Default")
      (node (ref "R31") (pin "2") (pinfunction "2_2") (pintype "bidirectional"))
      (node (ref "U5") (pin "30") (pinfunction "IO18_30") (pintype "bidirectional"))
      (node (ref "U8") (pin "4") (pinfunction "EN_4") (pintype "bidirectional"))
    )
    (net (code "25") (name "LED_PWM_2") (class "Default")
      (node (ref "R17") (pin "2") (pinfunction "2_2") (pintype "bidirectional"))
      (node (ref "U3") (pin "4") (pinfunction "EN_4") (pintype "bidirectional"))
      (node (ref "U5") (pin "31") (pinfunction "IO19_31") (pintype "bidirectional"))
    )
    (net (code "26") (name "LED_PWM_3") (class "Default")
      (node (ref "R10") (pin "2") (pinfunction "2_2") (pintype "bidirectional"))
      (node (ref "U2") (pin "4") (pinfunction "EN_4") (pintype "bidirectional"))
      (node (ref "U5") (pin "33") (pinfunction "IO21_33") (pintype "bidirectional"))
    )
    (net (code "27") (name "Net-(CN2-5V)") (class "Default")
      (node (ref "CN2") (pin "VCC") (pinfunction "5V_VCC") (pintype "bidirectional"))
      (node (ref "FB1") (pin "1") (pinfunction "1_1") (pintype "bidirectional"))
    )
    (net (code "28") (name "Net-(D2-PadA)") (class "Default")
      (node (ref "D2") (pin "A") (pinfunction "A_A") (pintype "bidirectional"))
      (node (ref "L2") (pin "2") (pinfunction "2_2") (pintype "bidirectional"))
      (node (ref "U2") (pin "1") (pinfunction "SW_1") (pintype "bidirectional"))
      (node (ref "U2") (pin "2") (pinfunction "SW_2") (pintype "bidirectional"))
    )
    (net (code "29") (name "Net-(D3-PadA)") (class "Default")
      (node (ref "D3") (pin "A") (pinfunction "A_A") (pintype "bidirectional"))
      (node (ref "L3") (pin "2") (pinfunction "2_2") (pintype "bidirectional"))
      (node (ref "U3") (pin "1") (pinfunction "SW_1") (pintype "bidirectional"))
      (node (ref "U3") (pin "2") (pinfunction "SW_2") (pintype "bidirectional"))
    )
    (net (code "30") (name "Net-(D5-PadA)") (class "Default")
      (node (ref "D5") (pin "A") (pinfunction "A_A") (pintype "bidirectional"))
      (node (ref "L5") (pin "2") (pinfunction "2_2") (pintype "bidirectional"))
      (node (ref "U8") (pin "1") (pinfunction "SW_1") (pintype "bidirectional"))
      (node (ref "U8") (pin "2") (pinfunction "SW_2") (pintype "bidirectional"))
    )
    (net (code "31") (name "Net-(D7-PadA)") (class "Default")
      (node (ref "D7") (pin "A") (pinfunction "A_A") (pintype "bidirectional"))
      (node (ref "L7") (pin "2") (pinfunction "2_2") (pintype "bidirectional"))
      (node (ref "U10") (pin "1") (pinfunction "SW_1") (pintype "bidirectional"))
      (node (ref "U10") (pin "2") (pinfunction "SW_2") (pintype "bidirectional"))
    )
    (net (code "32") (name "Net-(Q4-B)") (class "Default")
      (node (ref "Q4") (pin "1") (pinfunction "B_1") (pintype "bidirectional"))
      (node (ref "R21") (pin "1") (pinfunction "1_1") (pintype "bidirectional"))
    )
    (net (code "33") (name "Net-(Q5-B)") (class "Default")
      (node (ref "Q5") (pin "1") (pinfunction "B_1") (pintype "bidirectional"))
      (node (ref "R22") (pin "1") (pinfunction "1_1") (pintype "bidirectional"))
    )
    (net (code "34") (name "Net-(TP1-P$1)") (class "Default")
      (node (ref "D1") (pin "A") (pinfunction "A_A") (pintype "bidirectional"))
      (node (ref "D4") (pin "A") (pinfunction "A_A") (pintype "bidirectional"))
      (node (ref "TP1") (pin "1") (pinfunction "P$1_1") (pintype "bidirectional"))
    )
    (net (code "35") (name "Net-(U1-D+)") (class "Default")
      (node (ref "U1") (pin "4") (pinfunction "D+_4") (pintype "bidirectional"))
      (node (ref "U6") (pin "1") (pinfunction "D+_IN_1") (pintype "bidirectional"))
    )
    (net (code "36") (name "Net-(U1-D-)") (class "Default")
      (node (ref "U1") (pin "5") (pinfunction "D-_5") (pintype "bidirectional"))
      (node (ref "U6") (pin "3") (pinfunction "D-_IN_3") (pintype "bidirectional"))
    )
    (net (code "37") (name "Net-(U1-VBUS)") (class "Default")
      (node (ref "R1") (pin "2") (pinfunction "2_2") (pintype "bidirectional"))
      (node (ref "R2") (pin "2") (pinfunction "2_2") (pintype "bidirectional"))
      (node (ref "U1") (pin "8") (pinfunction "VBUS_8") (pintype "bidirectional"))
    )
    (net (code "38") (name "Net-(U1-VDD)") (class "Default")
      (node (ref "C1") (pin "2") (pinfunction "2_2") (pintype "bidirectional"))
      (node (ref "C2") (pin "2") (pinfunction "2_2") (pintype "bidirectional"))
      (node (ref "U1") (pin "6") (pinfunction "VDD_6") (pintype "bidirectional"))
      (node (ref "U1") (pin "7") (pinfunction "VREGIN_7") (pintype "bidirectional"))
    )
    (net (code "39") (name "Net-(U1-~{RST})") (class "Default")
      (node (ref "R4") (pin "1") (pinfunction "1_1") (pintype "bidirectional"))
      (node (ref "U1") (pin "9") (pinfunction "~{RST}_9") (pintype "bidirectional"))
    )
    (net (code "40") (name "Net-(U1-~{SUSPEND})") (class "Default")
      (node (ref "R3") (pin "2") (pinfunction "2_2") (pintype "bidirectional"))
      (node (ref "U1") (pin "11") (pinfunction "~{SUSPEND}_11") (pintype "bidirectional"))
    )
    (net (code "41") (name "Net-(U2-COMP)") (class "Default")
      (node (ref "C11") (pin "2") (pinfunction "2_2") (pintype "bidirectional"))
      (node (ref "U2") (pin "8") (pinfunction "COMP_8") (pintype "bidirectional"))
    )
    (net (code "42") (name "Net-(U2-DIMC)") (class "Default")
      (node (ref "C18") (pin "2") (pinfunction "2_2") (pintype "bidirectional"))
      (node (ref "U2") (pin "6") (pinfunction "DIMC_6") (pintype "bidirectional"))
    )
    (net (code "43") (name "Net-(U2-FREQ)") (class "Default")
      (node (ref "R9") (pin "2") (pinfunction "2_2") (pintype "bidirectional"))
      (node (ref "U2") (pin "10") (pinfunction "FREQ_10") (pintype "bidirectional"))
    )
    (net (code "44") (name "Net-(U2-OVP)") (class "Default")
      (node (ref "R6") (pin "1") (pinfunction "1_1") (pintype "bidirectional"))
      (node (ref "R7") (pin "2") (pinfunction "2_2") (pintype "bidirectional"))
      (node (ref "U2") (pin "11") (pinfunction "OVP_11") (pintype "bidirectional"))
    )
    (net (code "45") (name "Net-(U2-SS)") (class "Default")
      (node (ref "C10") (pin "2") (pinfunction "2_2") (pintype "bidirectional"))
      (node (ref "U2") (pin "5") (pinfunction "SS_5") (pintype "bidirectional"))
    )
    (net (code "46") (name "Net-(U3-COMP)") (class "Default")
      (node (ref "C25") (pin "2") (pinfunction "2_2") (pintype "bidirectional"))
      (node (ref "U3") (pin "8") (pinfunction "COMP_8") (pintype "bidirectional"))
    )
    (net (code "47") (name "Net-(U3-DIMC)") (class "Default")
      (node (ref "C26") (pin "2") (pinfunction "2_2") (pintype "bidirectional"))
      (node (ref "U3") (pin "6") (pinfunction "DIMC_6") (pintype "bidirectional"))
    )
    (net (code "48") (name "Net-(U3-FREQ)") (class "Default")
      (node (ref "R15") (pin "2") (pinfunction "2_2") (pintype "bidirectional"))
      (node (ref "U3") (pin "10") (pinfunction "FREQ_10") (pintype "bidirectional"))
    )
    (net (code "49") (name "Net-(U3-OVP)") (class "Default")
      (node (ref "R12") (pin "1") (pinfunction "1_1") (pintype "bidirectional"))
      (node (ref "R13") (pin "2") (pinfunction "2_2") (pintype "bidirectional"))
      (node (ref "U3") (pin "11") (pinfunction "OVP_11") (pintype "bidirectional"))
    )
    (net (code "50") (name "Net-(U3-SS)") (class "Default")
      (node (ref "C24") (pin "2") (pinfunction "2_2") (pintype "bidirectional"))
      (node (ref "U3") (pin "5") (pinfunction "SS_5") (pintype "bidirectional"))
    )
    (net (code "51") (name "Net-(U5-IO2)") (class "Default")
      (node (ref "R34") (pin "1") (pinfunction "1_1") (pintype "bidirectional"))
      (node (ref "U5") (pin "24") (pinfunction "IO2_24") (pintype "bidirectional"))
    )
    (net (code "52") (name "Net-(U6-D+_OUT)") (class "Default")
      (node (ref "CN2") (pin "D+") (pinfunction "D+_D+") (pintype "bidirectional"))
      (node (ref "U6") (pin "6") (pinfunction "D+_OUT_6") (pintype "bidirectional"))
    )
    (net (code "53") (name "Net-(U6-D-OUT)") (class "Default")
      (node (ref "CN2") (pin "D-") (pinfunction "D-_D-") (pintype "bidirectional"))
      (node (ref "U6") (pin "4") (pinfunction "D-OUT_4") (pintype "bidirectional"))
    )
    (net (code "54") (name "Net-(U8-COMP)") (class "Default")
      (node (ref "C39") (pin "2") (pinfunction "2_2") (pintype "bidirectional"))
      (node (ref "U8") (pin "8") (pinfunction "COMP_8") (pintype "bidirectional"))
    )
    (net (code "55") (name "Net-(U8-DIMC)") (class "Default")
      (node (ref "C40") (pin "2") (pinfunction "2_2") (pintype "bidirectional"))
      (node (ref "U8") (pin "6") (pinfunction "DIMC_6") (pintype "bidirectional"))
    )
    (net (code "56") (name "Net-(U8-FREQ)") (class "Default")
      (node (ref "R30") (pin "2") (pinfunction "2_2") (pintype "bidirectional"))
      (node (ref "U8") (pin "10") (pinfunction "FREQ_10") (pintype "bidirectional"))
    )
    (net (code "57") (name "Net-(U8-OVP)") (class "Default")
      (node (ref "R27") (pin "1") (pinfunction "1_1") (pintype "bidirectional"))
      (node (ref "R28") (pin "2") (pinfunction "2_2") (pintype "bidirectional"))
      (node (ref "U8") (pin "11") (pinfunction "OVP_11") (pintype "bidirectional"))
    )
    (net (code "58") (name "Net-(U8-SS)") (class "Default")
      (node (ref "C38") (pin "2") (pinfunction "2_2") (pintype "bidirectional"))
      (node (ref "U8") (pin "5") (pinfunction "SS_5") (pintype "bidirectional"))
    )
    (net (code "59") (name "Net-(U10-COMP)") (class "Default")
      (node (ref "C53") (pin "2") (pinfunction "2_2") (pintype "bidirectional"))
      (node (ref "U10") (pin "8") (pinfunction "COMP_8") (pintype "bidirectional"))
    )
    (net (code "60") (name "Net-(U10-DIMC)") (class "Default")
      (node (ref "C54") (pin "2") (pinfunction "2_2") (pintype "bidirectional"))
      (node (ref "U10") (pin "6") (pinfunction "DIMC_6") (pintype "bidirectional"))
    )
    (net (code "61") (name "Net-(U10-FREQ)") (class "Default")
      (node (ref "R40") (pin "2") (pinfunction "2_2") (pintype "bidirectional"))
      (node (ref "U10") (pin "10") (pinfunction "FREQ_10") (pintype "bidirectional"))
    )
    (net (code "62") (name "Net-(U10-OVP)") (class "Default")
      (node (ref "R37") (pin "1") (pinfunction "1_1") (pintype "bidirectional"))
      (node (ref "R38") (pin "2") (pinfunction "2_2") (pintype "bidirectional"))
      (node (ref "U10") (pin "11") (pinfunction "OVP_11") (pintype "bidirectional"))
    )
    (net (code "63") (name "Net-(U10-SS)") (class "Default")
      (node (ref "C52") (pin "2") (pinfunction "2_2") (pintype "bidirectional"))
      (node (ref "U10") (pin "5") (pinfunction "SS_5") (pintype "bidirectional"))
    )
    (net (code "64") (name "RS485_A") (class "Default")
      (node (ref "R18") (pin "2") (pinfunction "2_2") (pintype "bidirectional"))
      (node (ref "TP3") (pin "1") (pinfunction "P$1_1") (pintype "bidirectional"))
      (node (ref "U4") (pin "6") (pinfunction "A_6") (pintype "bidirectional"))
    )
    (net (code "65") (name "RS485_B") (class "Default")
      (node (ref "R18") (pin "1") (pinfunction "1_1") (pintype "bidirectional"))
      (node (ref "TP4") (pin "1") (pinfunction "P$1_1") (pintype "bidirectional"))
      (node (ref "U4") (pin "7") (pinfunction "B_7") (pintype "bidirectional"))
    )
    (net (code "66") (name "VIN") (class "Default")
      (node (ref "C19") (pin "2") (pinfunction "2_2") (pintype "bidirectional"))
      (node (ref "C23") (pin "2") (pinfunction "2_2") (pintype "bidirectional"))
      (node (ref "C27") (pin "2") (pinfunction "2_2") (pintype "bidirectional"))
      (node (ref "C31") (pin "2") (pinfunction "2_2") (pintype "bidirectional"))
      (node (ref "C37") (pin "2") (pinfunction "2_2") (pintype "bidirectional"))
      (node (ref "C41") (pin "2") (pinfunction "2_2") (pintype "bidirectional"))
      (node (ref "C51") (pin "2") (pinfunction "2_2") (pintype "bidirectional"))
      (node (ref "C55") (pin "2") (pinfunction "2_2") (pintype "bidirectional"))
      (node (ref "C7") (pin "2") (pinfunction "2_2") (pintype "bidirectional"))
      (node (ref "C9") (pin "2") (pinfunction "2_2") (pintype "bidirectional"))
      (node (ref "D1") (pin "K") (pinfunction "K_K") (pintype "bidirectional"))
      (node (ref "D4") (pin "K") (pinfunction "K_K") (pintype "bidirectional"))
      (node (ref "D6") (pin "K") (pinfunction "K_K") (pintype "bidirectional"))
      (node (ref "D9") (pin "K") (pinfunction "K_K") (pintype "bidirectional"))
      (node (ref "L2") (pin "1") (pinfunction "1_1") (pintype "bidirectional"))
      (node (ref "L3") (pin "1") (pinfunction "1_1") (pintype "bidirectional"))
      (node (ref "L5") (pin "1") (pinfunction "1_1") (pintype "bidirectional"))
      (node (ref "L7") (pin "1") (pinfunction "1_1") (pintype "bidirectional"))
      (node (ref "U10") (pin "3") (pinfunction "VIN_3") (pintype "bidirectional"))
      (node (ref "U11") (pin "3") (pinfunction "VIN_3") (pintype "bidirectional"))
      (node (ref "U11") (pin "4") (pinfunction "EN_4") (pintype "bidirectional"))
      (node (ref "U2") (pin "3") (pinfunction "VIN_3") (pintype "bidirectional"))
      (node (ref "U3") (pin "3") (pinfunction "VIN_3") (pintype "bidirectional"))
      (node (ref "U8") (pin "3") (pinfunction "VIN_3") (pintype "bidirectional"))
    )
    (net (code "67") (name "unconnected-(CN2-PadID)") (class "Default")
      (node (ref "CN2") (pin "ID") (pinfunction "ID_ID") (pintype "bidirectional"))
    )
    (net (code "68") (name "unconnected-(U1-CHR0-Pad15)") (class "Default")
      (node (ref "U1") (pin "15") (pinfunction "CHR0_15") (pintype "bidirectional"))
    )
    (net (code "69") (name "unconnected-(U1-CHR1-Pad14)") (class "Default")
      (node (ref "U1") (pin "14") (pinfunction "CHR1_14") (pintype "bidirectional"))
    )
    (net (code "70") (name "unconnected-(U1-CHREN-Pad13)") (class "Default")
      (node (ref "U1") (pin "13") (pinfunction "CHREN_13") (pintype "bidirectional"))
    )
    (net (code "71") (name "unconnected-(U1-CTS-Pad23)") (class "Default")
      (node (ref "U1") (pin "23") (pinfunction "CTS_23") (pintype "bidirectional"))
    )
    (net (code "72") (name "unconnected-(U1-DCD-Pad1)") (class "Default")
      (node (ref "U1") (pin "1") (pinfunction "DCD_1") (pintype "bidirectional"))
    )
    (net (code "73") (name "unconnected-(U1-DSR-Pad27)") (class "Default")
      (node (ref "U1") (pin "27") (pinfunction "DSR_27") (pintype "bidirectional"))
    )
    (net (code "74") (name "unconnected-(U1-GPIO0{slash}TXT-Pad19)") (class "Default")
      (node (ref "U1") (pin "19") (pinfunction "GPIO0/TXT_19") (pintype "bidirectional"))
    )
    (net (code "75") (name "unconnected-(U1-GPIO1{slash}RXT-Pad18)") (class "Default")
      (node (ref "U1") (pin "18") (pinfunction "GPIO1/RXT_18") (pintype "bidirectional"))
    )
    (net (code "76") (name "unconnected-(U1-GPIO2{slash}RS485-Pad17)") (class "Default")
      (node (ref "U1") (pin "17") (pinfunction "GPIO2/RS485_17") (pintype "bidirectional"))
    )
    (net (code "77") (name "unconnected-(U1-GPIO3{slash}WKUP-Pad16)") (class "Default")
      (node (ref "U1") (pin "16") (pinfunction "GPIO3/WKUP_16") (pintype "bidirectional"))
    )
    (net (code "78") (name "unconnected-(U1-GPIO4-Pad22)") (class "Default")
      (node (ref "U1") (pin "22") (pinfunction "GPIO4_22") (pintype "bidirectional"))
    )
    (net (code "79") (name "unconnected-(U1-GPIO5-Pad21)") (class "Default")
      (node (ref "U1") (pin "21") (pinfunction "GPIO5_21") (pintype "bidirectional"))
    )
    (net (code "80") (name "unconnected-(U1-GPIO6-Pad20)") (class "Default")
      (node (ref "U1") (pin "20") (pinfunction "GPIO6_20") (pintype "bidirectional"))
    )
    (net (code "81") (name "unconnected-(U1-RI{slash}CLK-Pad2)") (class "Default")
      (node (ref "U1") (pin "2") (pinfunction "RI/CLK_2") (pintype "bidirectional"))
    )
    (net (code "82") (name "unconnected-(U1-SUSPEND-Pad12)") (class "Default")
      (node (ref "U1") (pin "12") (pinfunction "SUSPEND_12") (pintype "bidirectional"))
    )
    (net (code "83") (name "unconnected-(U5-IO12-Pad14)") (class "Default")
      (node (ref "U5") (pin "14") (pinfunction "IO12_14") (pintype "bidirectional"))
    )
    (net (code "84") (name "unconnected-(U5-IO14-Pad13)") (class "Default")
      (node (ref "U5") (pin "13") (pinfunction "IO14_13") (pintype "bidirectional"))
    )
    (net (code "85") (name "unconnected-(U5-IO22-Pad36)") (class "Default")
      (node (ref "U5") (pin "36") (pinfunction "IO22_36") (pintype "bidirectional"))
    )
    (net (code "86") (name "unconnected-(U5-IO23-Pad37)") (class "Default")
      (node (ref "U5") (pin "37") (pinfunction "IO23_37") (pintype "bidirectional"))
    )
    (net (code "87") (name "unconnected-(U5-IO25-Pad10)") (class "Default")
      (node (ref "U5") (pin "10") (pinfunction "IO25_10") (pintype "bidirectional"))
    )
    (net (code "88") (name "unconnected-(U5-IO26-Pad11)") (class "Default")
      (node (ref "U5") (pin "11") (pinfunction "IO26_11") (pintype "bidirectional"))
    )
    (net (code "89") (name "unconnected-(U5-IO27-Pad12)") (class "Default")
      (node (ref "U5") (pin "12") (pinfunction "IO27_12") (pintype "bidirectional"))
    )
    (net (code "90") (name "unconnected-(U5-IO32-Pad8)") (class "Default")
      (node (ref "U5") (pin "8") (pinfunction "IO32_8") (pintype "bidirectional"))
    )
    (net (code "91") (name "unconnected-(U5-IO33-Pad9)") (class "Default")
      (node (ref "U5") (pin "9") (pinfunction "IO33_9") (pintype "bidirectional"))
    )
    (net (code "92") (name "unconnected-(U5-IO34-Pad6)") (class "Default")
      (node (ref "U5") (pin "6") (pinfunction "IO34_6") (pintype "bidirectional"))
    )
    (net (code "93") (name "unconnected-(U5-IO35-Pad7)") (class "Default")
      (node (ref "U5") (pin "7") (pinfunction "IO35_7") (pintype "bidirectional"))
    )
    (net (code "94") (name "unconnected-(U5-SCK{slash}CLK-Pad20)") (class "Default")
      (node (ref "U5") (pin "20") (pinfunction "SCK/CLK_20") (pintype "bidirectional"))
    )
    (net (code "95") (name "unconnected-(U5-SCS{slash}CMD-Pad19)") (class "Default")
      (node (ref "U5") (pin "19") (pinfunction "SCS/CMD_19") (pintype "bidirectional"))
    )
    (net (code "96") (name "unconnected-(U5-SDI{slash}SD1-Pad22)") (class "Default")
      (node (ref "U5") (pin "22") (pinfunction "SDI/SD1_22") (pintype "bidirectional"))
    )
    (net (code "97") (name "unconnected-(U5-SDO{slash}SD0-Pad21)") (class "Default")
      (node (ref "U5") (pin "21") (pinfunction "SDO/SD0_21") (pintype "bidirectional"))
    )
    (net (code "98") (name "unconnected-(U5-SENSOR_VN-Pad5)") (class "Default")
      (node (ref "U5") (pin "5") (pinfunction "SENSOR_VN_5") (pintype "bidirectional"))
    )
    (net (code "99") (name "unconnected-(U5-SENSOR_VP-Pad4)") (class "Default")
      (node (ref "U5") (pin "4") (pinfunction "SENSOR_VP_4") (pintype "bidirectional"))
    )
    (net (code "100") (name "unconnected-(U5-SHD{slash}SD2-Pad17)") (class "Default")
      (node (ref "U5") (pin "17") (pinfunction "SHD/SD2_17") (pintype "bidirectional"))
    )
    (net (code "101") (name "unconnected-(U5-SWP{slash}SD3-Pad18)") (class "Default")
      (node (ref "U5") (pin "18") (pinfunction "SWP/SD3_18") (pintype "bidirectional"))
    )
    (net (code "102") (name "unconnected-(U11-PGOOD-Pad5)") (class "Default")
      (node (ref "U11") (pin "5") (pinfunction "PGOOD_5") (pintype "bidirectional"))
    )
  )
)
